# robot.net
KiCad netlist of a schematic drawn in EAGLE
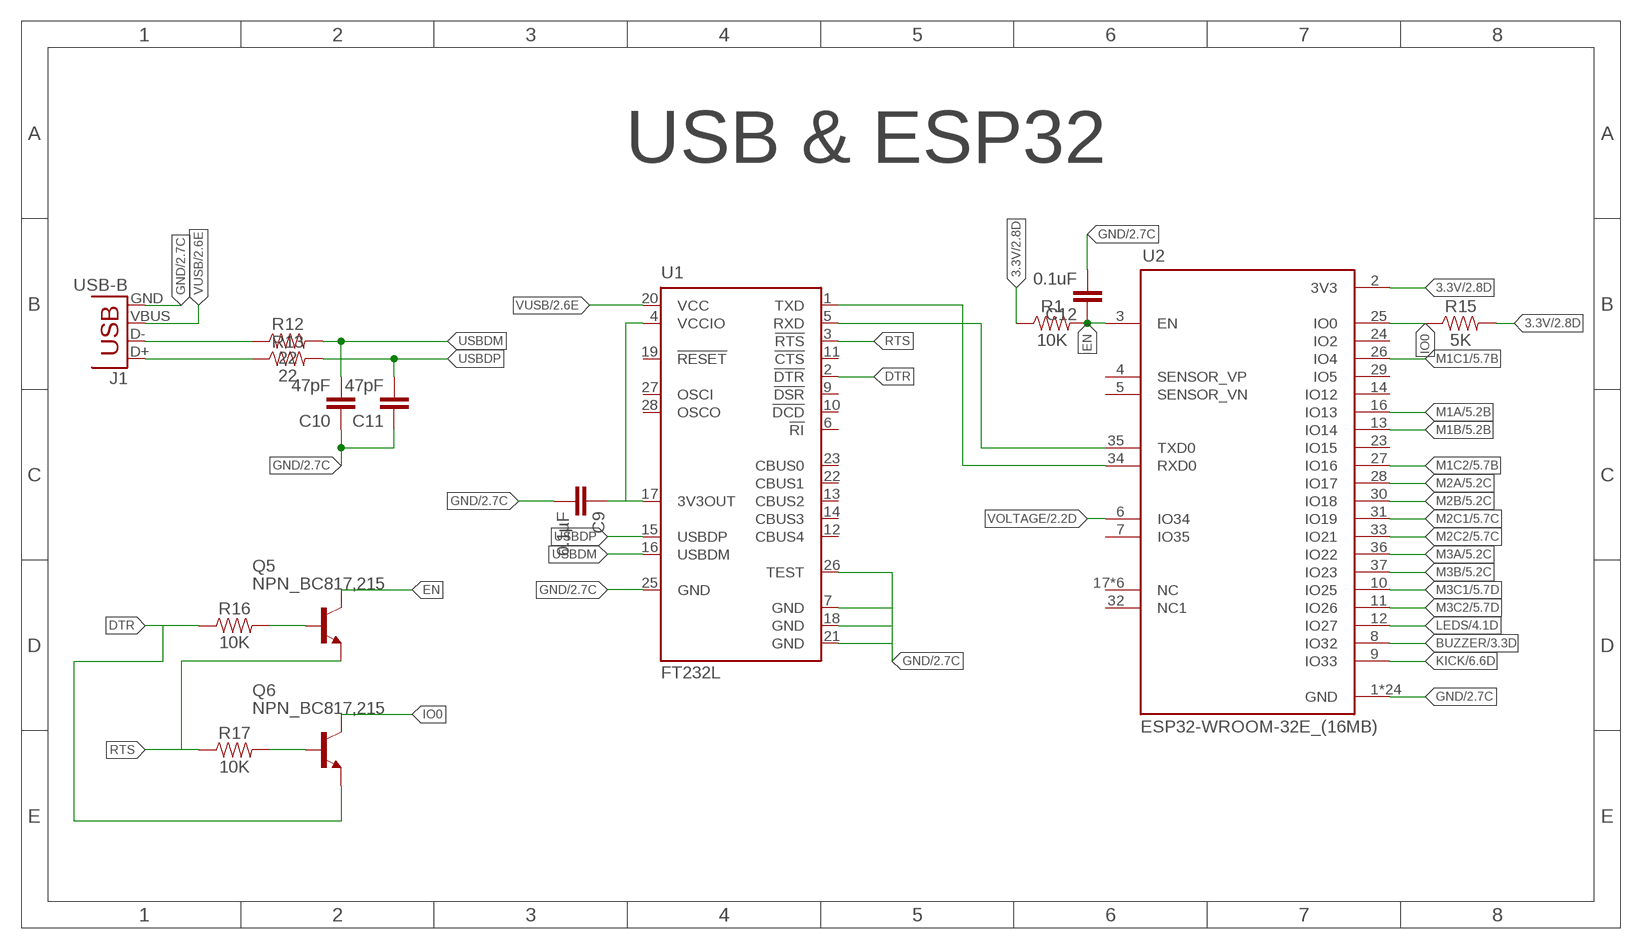
[diagram p0: schematic, sheet 1]
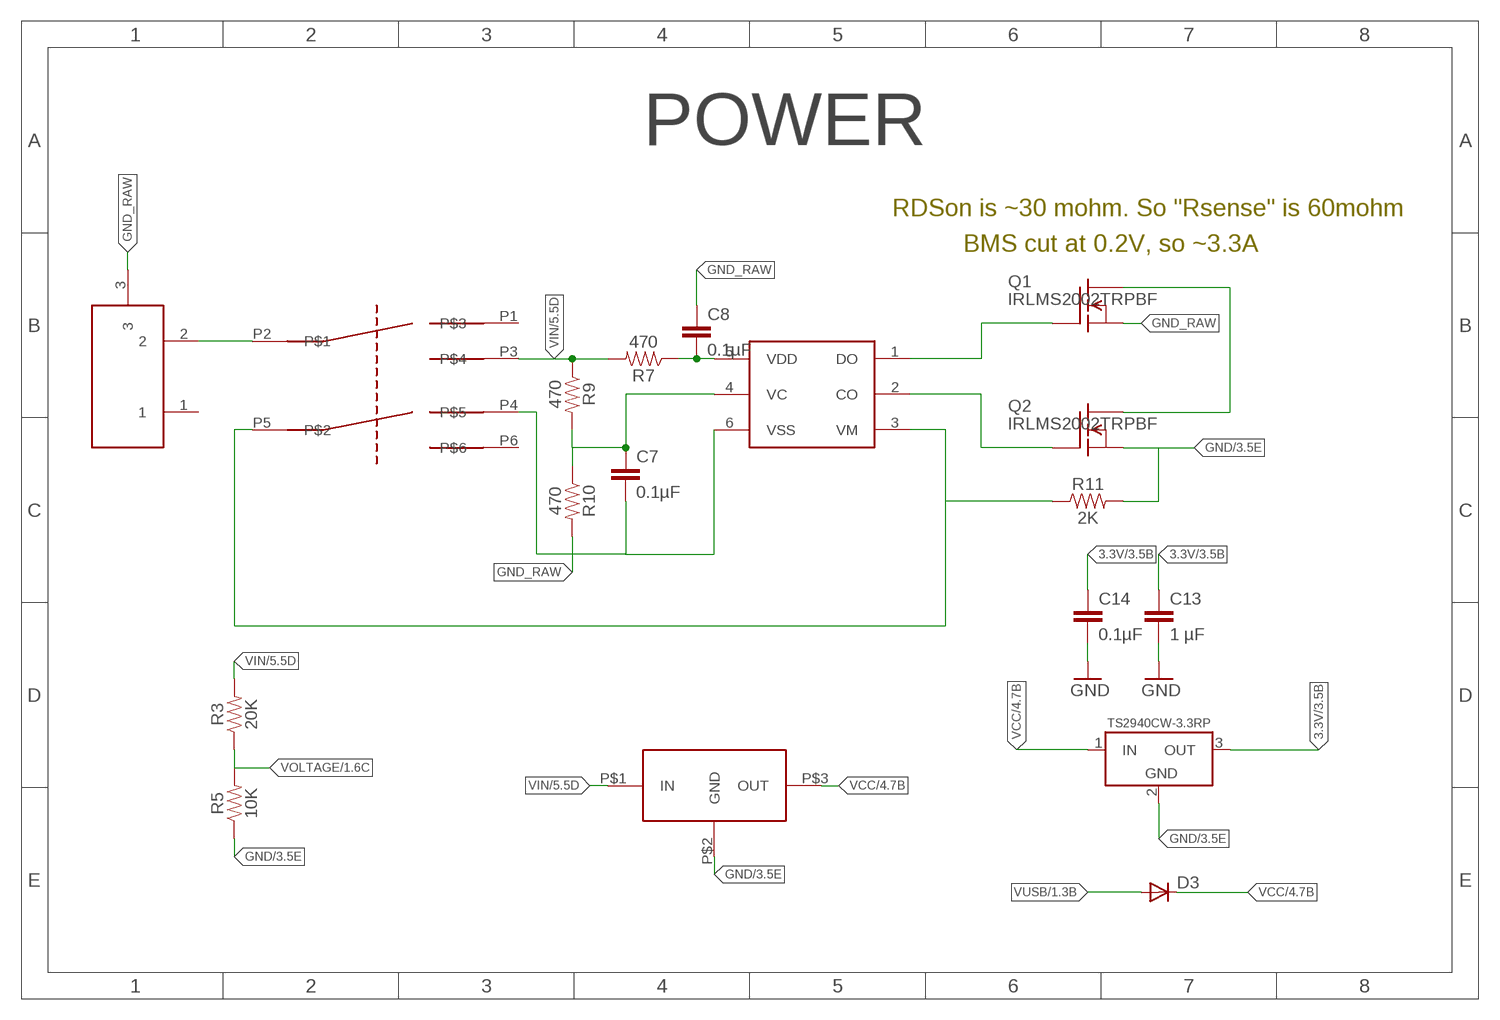
[diagram p1: schematic, sheet 2]
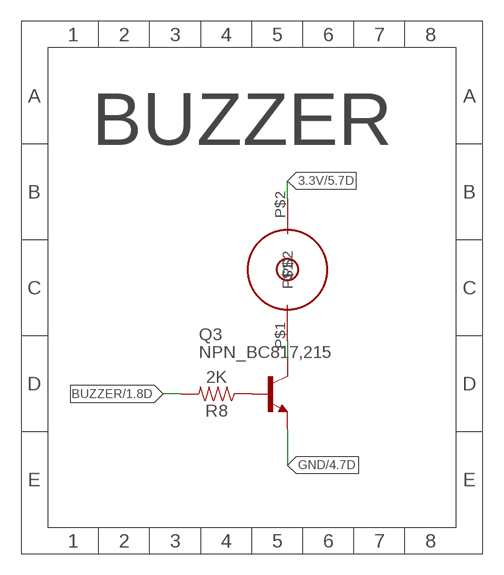
[diagram p2: schematic, sheet 3]
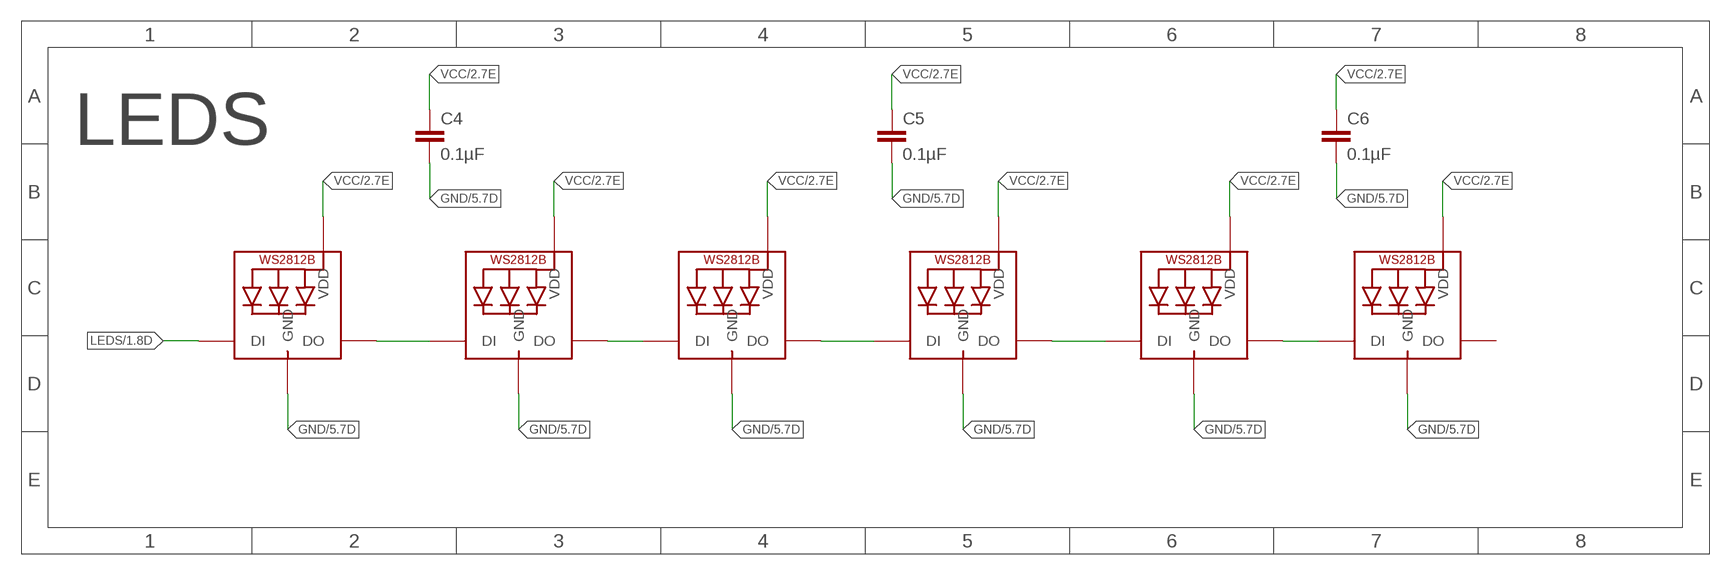
[diagram p3: schematic, sheet 4]
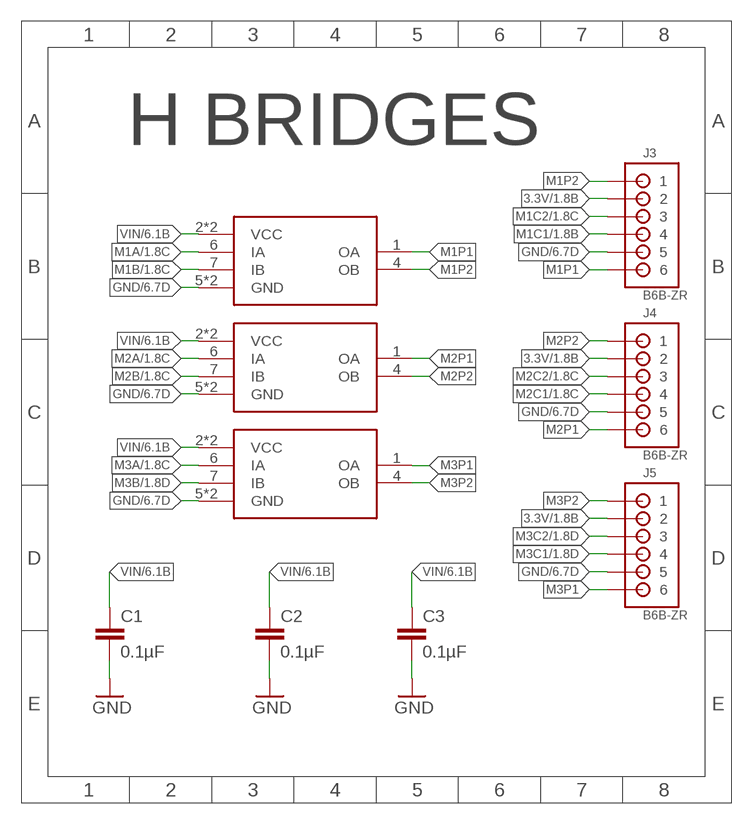
[diagram p4: schematic, sheet 5]
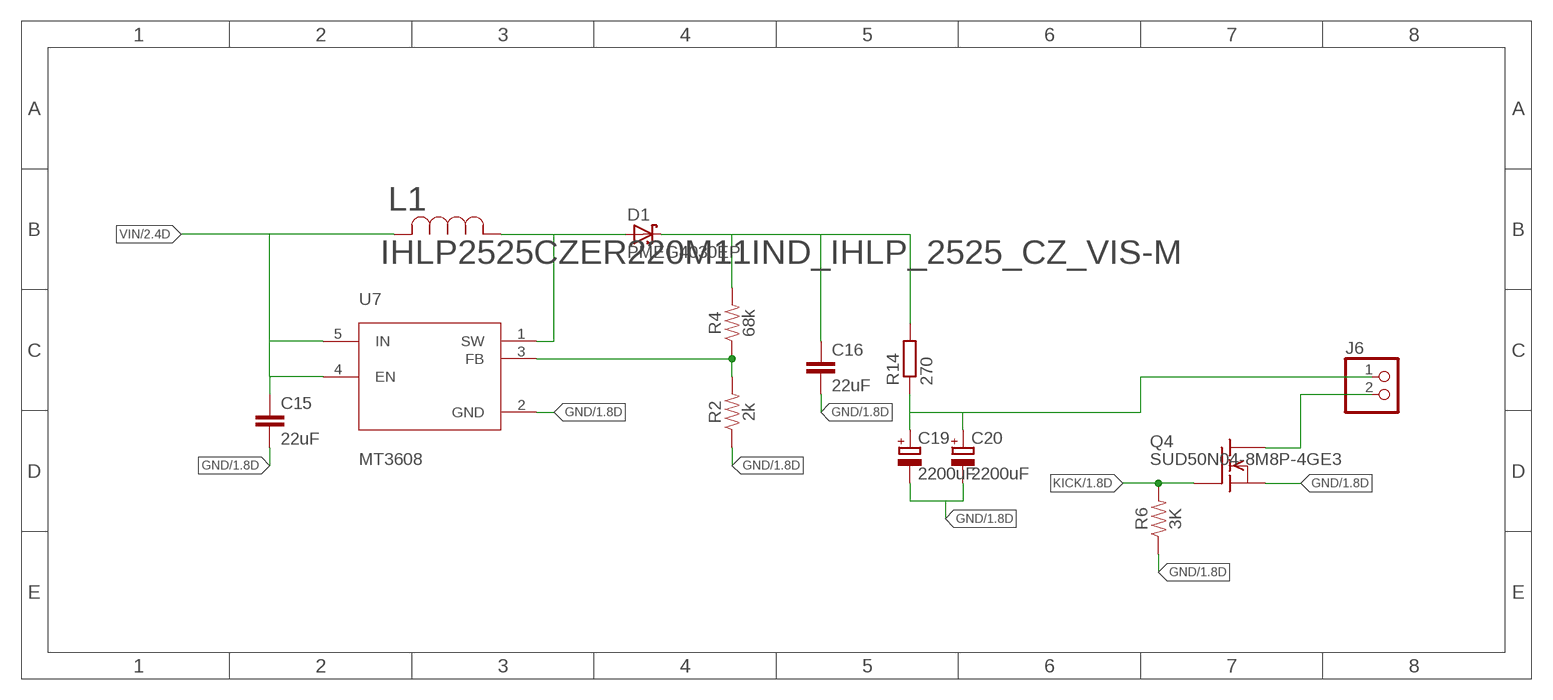
[diagram p5: schematic, sheet 6]

(export (version "E")
  (design (tool "Eeschema 10.0.6"))
  (components
    (comp (ref "C1")
      (value "0.1µF")
      (footprint "eagle-import:0805")
      (libsource (lib "eagle-import") (part "0.33UF/330NF-0805-50V-10%"))
    )
    (comp (ref "C2")
      (value "0.1µF")
      (footprint "eagle-import:0805")
      (fields (field (name "PROD_ID") "CAP-08469"))
      (libsource (lib "eagle-import") (part "0.33UF/330NF-0805-50V-10%"))
    )
    (comp (ref "C3")
      (value "0.1µF")
      (footprint "eagle-import:0805")
      (fields (field (name "PROD_ID") "CAP-08469"))
      (libsource (lib "eagle-import") (part "0.33UF/330NF-0805-50V-10%"))
    )
    (comp (ref "J3")
      (value "B6B-ZR")
      (footprint "eagle-import:B6B-ZR")
      (libsource (lib "eagle-import") (part "B6B-ZR"))
    )
    (comp (ref "J4")
      (value "B6B-ZR")
      (footprint "eagle-import:B6B-ZR")
      (libsource (lib "eagle-import") (part "B6B-ZR"))
    )
    (comp (ref "J5")
      (value "B6B-ZR")
      (footprint "eagle-import:B6B-ZR")
      (libsource (lib "eagle-import") (part "B6B-ZR"))
    )
    (comp (ref "U4")
      (value "L9110")
      (footprint "eagle-import:SO8")
      (libsource (lib "eagle-import") (part "L9110"))
    )
    (comp (ref "U5")
      (value "L9110")
      (footprint "eagle-import:SO8")
      (libsource (lib "eagle-import") (part "L9110"))
    )
    (comp (ref "U6")
      (value "L9110")
      (footprint "eagle-import:SO8")
      (libsource (lib "eagle-import") (part "L9110"))
    )
    (comp (ref "B1")
      (value "BUZZER66")
      (footprint "eagle-import:BUZZER66")
      (libsource (lib "eagle-import") (part "BUZZER66"))
    )
    (comp (ref "Q3")
      (value "NPN_BC817,215")
      (footprint "eagle-import:SOT-23")
      (libsource (lib "eagle-import") (part "NPN_BC817,215"))
    )
    (comp (ref "R8")
      (value "2K")
      (footprint "eagle-import:0805")
      (libsource (lib "eagle-import") (part "0.3OHM-0805-1/8W-1%"))
    )
    (comp (ref "C9")
      (value "0.1µF")
      (footprint "eagle-import:0805")
      (libsource (lib "eagle-import") (part "0.33UF/330NF-0805-50V-10%"))
    )
    (comp (ref "C10")
      (value "47pF")
      (footprint "eagle-import:0805")
      (libsource (lib "eagle-import") (part "CAP0805"))
    )
    (comp (ref "C11")
      (value "47pF")
      (footprint "eagle-import:0805")
      (libsource (lib "eagle-import") (part "CAP0805"))
    )
    (comp (ref "C12")
      (value "0.1uF")
      (footprint "eagle-import:0805")
      (libsource (lib "eagle-import") (part "CAP0805"))
    )
    (comp (ref "J1")
      (value "USB-B")
      (footprint "eagle-import:USB-B-PTH")
      (libsource (lib "eagle-import") (part "USBPTH"))
    )
    (comp (ref "Q5")
      (value "NPN_BC817,215")
      (footprint "eagle-import:SOT-23")
      (libsource (lib "eagle-import") (part "NPN_BC817,215"))
    )
    (comp (ref "Q6")
      (value "NPN_BC817,215")
      (footprint "eagle-import:SOT-23")
      (libsource (lib "eagle-import") (part "NPN_BC817,215"))
    )
    (comp (ref "R1")
      (value "10K")
      (footprint "eagle-import:0805")
      (fields (field (name "PROD_ID") "RES-11622"))
      (libsource (lib "eagle-import") (part "0.3OHM-0805-1/8W-1%"))
    )
    (comp (ref "R12")
      (value "22")
      (footprint "eagle-import:0805")
      (libsource (lib "eagle-import") (part "0.3OHM-0805-1/8W-1%"))
    )
    (comp (ref "R13")
      (value "22")
      (footprint "eagle-import:0805")
      (fields (field (name "PROD_ID") "RES-11622"))
      (libsource (lib "eagle-import") (part "0.3OHM-0805-1/8W-1%"))
    )
    (comp (ref "R15")
      (value "5K")
      (footprint "eagle-import:0805")
      (fields (field (name "PROD_ID") "RES-11622"))
      (libsource (lib "eagle-import") (part "0.3OHM-0805-1/8W-1%"))
    )
    (comp (ref "R16")
      (value "10K")
      (footprint "eagle-import:0805")
      (fields (field (name "PROD_ID") "RES-11622"))
      (libsource (lib "eagle-import") (part "0.3OHM-0805-1/8W-1%"))
    )
    (comp (ref "R17")
      (value "10K")
      (footprint "eagle-import:0805")
      (fields (field (name "PROD_ID") "RES-11622"))
      (libsource (lib "eagle-import") (part "0.3OHM-0805-1/8W-1%"))
    )
    (comp (ref "U1")
      (value "FT232L")
      (footprint "eagle-import:SSOP28")
      (fields (field (name "MPN") "FT232RL"))
      (libsource (lib "eagle-import") (part "FT232L"))
    )
    (comp (ref "U2")
      (value "ESP32-WROOM-32E_(16MB)")
      (footprint "eagle-import:MODULE_ESP32-WROOM-32E_(16MB)")
      (fields (field (name "MF") "Espressif Systems") (field (name "MP") "ESP32-WROOM-32E (16MB)"))
      (libsource (lib "eagle-import") (part "ESP32-WROOM-32E_(16MB)"))
    )
    (comp (ref "C4")
      (value "0.1µF")
      (footprint "eagle-import:0805")
      (libsource (lib "eagle-import") (part "0.33UF/330NF-0805-50V-10%"))
    )
    (comp (ref "C5")
      (value "0.1µF")
      (footprint "eagle-import:0805")
      (fields (field (name "PROD_ID") "CAP-08469"))
      (libsource (lib "eagle-import") (part "0.33UF/330NF-0805-50V-10%"))
    )
    (comp (ref "C6")
      (value "0.1µF")
      (footprint "eagle-import:0805")
      (fields (field (name "PROD_ID") "CAP-08469"))
      (libsource (lib "eagle-import") (part "0.33UF/330NF-0805-50V-10%"))
    )
    (comp (ref "LED1")
      (value "WS2812B5050")
      (footprint "eagle-import:WS2812B")
      (libsource (lib "eagle-import") (part "WS2812B5050"))
    )
    (comp (ref "LED2")
      (value "WS2812B5050")
      (footprint "eagle-import:WS2812B")
      (libsource (lib "eagle-import") (part "WS2812B5050"))
    )
    (comp (ref "LED3")
      (value "WS2812B5050")
      (footprint "eagle-import:WS2812B")
      (libsource (lib "eagle-import") (part "WS2812B5050"))
    )
    (comp (ref "LED4")
      (value "WS2812B5050")
      (footprint "eagle-import:WS2812B")
      (libsource (lib "eagle-import") (part "WS2812B5050"))
    )
    (comp (ref "LED5")
      (value "WS2812B5050")
      (footprint "eagle-import:WS2812B")
      (libsource (lib "eagle-import") (part "WS2812B5050"))
    )
    (comp (ref "LED6")
      (value "WS2812B5050")
      (footprint "eagle-import:WS2812B")
      (libsource (lib "eagle-import") (part "WS2812B5050"))
    )
    (comp (ref "C15")
      (value "22uF")
      (footprint "eagle-import:C0805")
      (libsource (lib "eagle-import") (part "C-EUC0805"))
    )
    (comp (ref "C16")
      (value "22uF")
      (footprint "eagle-import:C0805")
      (libsource (lib "eagle-import") (part "C-EUC0805"))
    )
    (comp (ref "C19")
      (value "2200uF")
      (footprint "eagle-import:E5-13")
      (libsource (lib "eagle-import") (part "CPOL-EUE5-13"))
    )
    (comp (ref "C20")
      (value "2200uF")
      (footprint "eagle-import:E5-13")
      (libsource (lib "eagle-import") (part "CPOL-EUE5-13"))
    )
    (comp (ref "D1")
      (value "PMEG4030EP")
      (footprint "eagle-import:SOD128")
      (libsource (lib "eagle-import") (part "PMEG4030EP"))
    )
    (comp (ref "J6")
      (value "KICKER")
      (footprint "eagle-import:KICKER")
      (libsource (lib "eagle-import") (part "KICKER"))
    )
    (comp (ref "L1")
      (value "IHLP2525CZER220M11IND_IHLP_2525_CZ_VIS-M")
      (footprint "eagle-import:IND_IHLP_2525_CZ_VIS-M")
      (fields (field (name "MANUFACTURER_PART_NUMBER") "IHLP2525CZER220M11"))
      (libsource (lib "eagle-import") (part "IHLP2525CZER220M11IND_IHLP_2525_CZ_VIS-M"))
    )
    (comp (ref "Q4")
      (value "SUD50N04-8M8P-4GE3")
      (footprint "eagle-import:TO252")
      (libsource (lib "eagle-import") (part "SUD50N04-8M8P-4GE3"))
    )
    (comp (ref "R2")
      (value "2k")
      (footprint "eagle-import:0805")
      (libsource (lib "eagle-import") (part "0.3OHM-0805-1/8W-1%"))
    )
    (comp (ref "R4")
      (value "68k")
      (footprint "eagle-import:0805")
      (libsource (lib "eagle-import") (part "0.3OHM-0805-1/8W-1%"))
    )
    (comp (ref "R6")
      (value "3K")
      (footprint "eagle-import:0805")
      (fields (field (name "PROD_ID") "RES-11622"))
      (libsource (lib "eagle-import") (part "0.3OHM-0805-1/8W-1%"))
    )
    (comp (ref "R14")
      (value "270")
      (footprint "eagle-import:R2010")
      (libsource (lib "eagle-import") (part "R-EU_R2010"))
    )
    (comp (ref "U7")
      (value "MT3608")
      (footprint "eagle-import:SOT95P280X145-6N")
      (fields (field (name "MF") "Aerosemi Technology Co., Ltd"))
      (libsource (lib "eagle-import") (part "MT3608"))
    )
    (comp (ref "C7")
      (value "0.1µF")
      (footprint "eagle-import:0805")
      (libsource (lib "eagle-import") (part "0.33UF/330NF-0805-50V-10%"))
    )
    (comp (ref "C8")
      (value "0.1µF")
      (footprint "eagle-import:0805")
      (fields (field (name "PROD_ID") "CAP-08469"))
      (libsource (lib "eagle-import") (part "0.33UF/330NF-0805-50V-10%"))
    )
    (comp (ref "C13")
      (value "1 µF")
      (footprint "eagle-import:0805")
      (fields (field (name "PROD_ID") "CAP-08469"))
      (libsource (lib "eagle-import") (part "0.33UF/330NF-0805-50V-10%"))
    )
    (comp (ref "C14")
      (value "0.1µF")
      (footprint "eagle-import:0805")
      (fields (field (name "PROD_ID") "CAP-08469"))
      (libsource (lib "eagle-import") (part "0.33UF/330NF-0805-50V-10%"))
    )
    (comp (ref "D3")
      (value "DIODESOD")
      (footprint "eagle-import:SOD-323")
      (libsource (lib "eagle-import") (part "DIODESOD"))
    )
    (comp (ref "J2")
      (value "DC21MMX")
      (footprint "eagle-import:DC-21MM")
      (libsource (lib "eagle-import") (part "DC21MMX"))
    )
    (comp (ref "Q1")
      (value "IRLMS2002TRPBF")
      (footprint "eagle-import:SOT23-6")
      (libsource (lib "eagle-import") (part "IRLMS2002TRPBF"))
    )
    (comp (ref "Q2")
      (value "IRLMS2002TRPBF")
      (footprint "eagle-import:SOT23-6")
      (libsource (lib "eagle-import") (part "IRLMS2002TRPBF"))
    )
    (comp (ref "R3")
      (value "20K")
      (footprint "eagle-import:0805")
      (libsource (lib "eagle-import") (part "0.3OHM-0805-1/8W-1%"))
    )
    (comp (ref "R5")
      (value "10K")
      (footprint "eagle-import:0805")
      (libsource (lib "eagle-import") (part "0.3OHM-0805-1/8W-1%"))
    )
    (comp (ref "R7")
      (value "470")
      (footprint "eagle-import:0805")
      (libsource (lib "eagle-import") (part "0.3OHM-0805-1/8W-1%"))
    )
    (comp (ref "R9")
      (value "470")
      (footprint "eagle-import:0805")
      (libsource (lib "eagle-import") (part "0.3OHM-0805-1/8W-1%"))
    )
    (comp (ref "R10")
      (value "470")
      (footprint "eagle-import:0805")
      (libsource (lib "eagle-import") (part "0.3OHM-0805-1/8W-1%"))
    )
    (comp (ref "R11")
      (value "2K")
      (footprint "eagle-import:0805")
      (libsource (lib "eagle-import") (part "0.3OHM-0805-1/8W-1%"))
    )
    (comp (ref "REG1")
      (value "REG_5V")
      (footprint "eagle-import:TRACOPOWER")
      (libsource (lib "eagle-import") (part "REG_5V"))
    )
    (comp (ref "S1")
      (value "DPDT")
      (footprint "eagle-import:L202021MA04Q")
      (libsource (lib "eagle-import") (part "DPDT"))
    )
    (comp (ref "U$25")
      (value "TS2940CW-3.3RP")
      (footprint "eagle-import:SOT223")
      (libsource (lib "eagle-import") (part "TS2940CW-3.3RP"))
    )
    (comp (ref "U3")
      (value "S8252")
      (footprint "eagle-import:SOT23-6")
      (libsource (lib "eagle-import") (part "S8252"))
    )
  )
  (nets
    (net (code "1") (name "1") (class "Default")
      (node (ref "J2") (pin "1") (pinfunction "1_1") (pintype "power_in"))
    )
    (net (code "2") (name "3.3V") (class "Default")
      (node (ref "B1") (pin "P$2") (pinfunction "P$2_P$2") (pintype "bidirectional"))
      (node (ref "C13") (pin "1") (pinfunction "1_1") (pintype "passive"))
      (node (ref "C14") (pin "1") (pinfunction "1_1") (pintype "passive"))
      (node (ref "J3") (pin "2") (pinfunction "2_2") (pintype "bidirectional"))
      (node (ref "J4") (pin "2") (pinfunction "2_2") (pintype "bidirectional"))
      (node (ref "J5") (pin "2") (pinfunction "2_2") (pintype "bidirectional"))
      (node (ref "R1") (pin "1") (pinfunction "1_1") (pintype "passive"))
      (node (ref "R15") (pin "2") (pinfunction "2_2") (pintype "passive"))
      (node (ref "U$25") (pin "3") (pinfunction "OUT_3") (pintype "output"))
      (node (ref "U2") (pin "2") (pinfunction "3V3_2") (pintype "power_in"))
    )
    (net (code "3") (name "BUZZER") (class "Default")
      (node (ref "R8") (pin "2") (pinfunction "2_2") (pintype "passive"))
      (node (ref "U2") (pin "8") (pinfunction "IO32_8") (pintype "bidirectional"))
    )
    (net (code "4") (name "DTR") (class "Default")
      (node (ref "Q6") (pin "2") (pinfunction "E_2") (pintype "passive"))
      (node (ref "R16") (pin "1") (pinfunction "1_1") (pintype "passive"))
      (node (ref "U1") (pin "2") (pinfunction "~{DTR}_2") (pintype "output"))
    )
    (net (code "5") (name "EN") (class "Default")
      (node (ref "C12") (pin "1") (pinfunction "1_1") (pintype "passive"))
      (node (ref "Q5") (pin "3") (pinfunction "C_3") (pintype "passive"))
      (node (ref "R1") (pin "2") (pinfunction "2_2") (pintype "passive"))
      (node (ref "U2") (pin "3") (pinfunction "EN_3") (pintype "input"))
    )
    (net (code "6") (name "GND") (class "Default")
      (node (ref "C1") (pin "2") (pinfunction "2_2") (pintype "passive"))
      (node (ref "C10") (pin "1") (pinfunction "1_1") (pintype "passive"))
      (node (ref "C11") (pin "1") (pinfunction "1_1") (pintype "passive"))
      (node (ref "C12") (pin "2") (pinfunction "2_2") (pintype "passive"))
      (node (ref "C13") (pin "2") (pinfunction "2_2") (pintype "passive"))
      (node (ref "C14") (pin "2") (pinfunction "2_2") (pintype "passive"))
      (node (ref "C15") (pin "2") (pinfunction "2_2") (pintype "passive"))
      (node (ref "C16") (pin "2") (pinfunction "2_2") (pintype "passive"))
      (node (ref "C19") (pin "-") (pinfunction "-_-") (pintype "passive"))
      (node (ref "C2") (pin "2") (pinfunction "2_2") (pintype "passive"))
      (node (ref "C20") (pin "-") (pinfunction "-_-") (pintype "passive"))
      (node (ref "C3") (pin "2") (pinfunction "2_2") (pintype "passive"))
      (node (ref "C4") (pin "2") (pinfunction "2_2") (pintype "passive"))
      (node (ref "C5") (pin "2") (pinfunction "2_2") (pintype "passive"))
      (node (ref "C6") (pin "2") (pinfunction "2_2") (pintype "passive"))
      (node (ref "C9") (pin "2") (pinfunction "2_2") (pintype "passive"))
      (node (ref "J1") (pin "GND") (pinfunction "GND_GND") (pintype "bidirectional"))
      (node (ref "J3") (pin "5") (pinfunction "5_5") (pintype "bidirectional"))
      (node (ref "J4") (pin "5") (pinfunction "5_5") (pintype "bidirectional"))
      (node (ref "J5") (pin "5") (pinfunction "5_5") (pintype "bidirectional"))
      (node (ref "LED1") (pin "3-GND") (pinfunction "GND_3-GND") (pintype "power_in"))
      (node (ref "LED2") (pin "3-GND") (pinfunction "GND_3-GND") (pintype "power_in"))
      (node (ref "LED3") (pin "3-GND") (pinfunction "GND_3-GND") (pintype "power_in"))
      (node (ref "LED4") (pin "3-GND") (pinfunction "GND_3-GND") (pintype "power_in"))
      (node (ref "LED5") (pin "3-GND") (pinfunction "GND_3-GND") (pintype "power_in"))
      (node (ref "LED6") (pin "3-GND") (pinfunction "GND_3-GND") (pintype "power_in"))
      (node (ref "Q2") (pin "4") (pinfunction "S_4") (pintype "passive"))
      (node (ref "Q3") (pin "2") (pinfunction "E_2") (pintype "passive"))
      (node (ref "Q4") (pin "2") (pinfunction "S_2") (pintype "passive"))
      (node (ref "R11") (pin "2") (pinfunction "2_2") (pintype "passive"))
      (node (ref "R2") (pin "1") (pinfunction "1_1") (pintype "passive"))
      (node (ref "R5") (pin "1") (pinfunction "1_1") (pintype "passive"))
      (node (ref "R6") (pin "1") (pinfunction "1_1") (pintype "passive"))
      (node (ref "REG1") (pin "P$2") (pinfunction "GND_P$2") (pintype "bidirectional"))
      (node (ref "U$25") (pin "2") (pinfunction "GND_2") (pintype "power_in"))
      (node (ref "U1") (pin "18") (pinfunction "GND_18") (pintype "power_in"))
      (node (ref "U1") (pin "21") (pinfunction "GND_21") (pintype "power_in"))
      (node (ref "U1") (pin "25") (pinfunction "GND_25") (pintype "power_in"))
      (node (ref "U1") (pin "26") (pinfunction "TEST_26") (pintype "input"))
      (node (ref "U1") (pin "7") (pinfunction "GND_7") (pintype "power_in"))
      (node (ref "U2") (pin "1") (pinfunction "GND_1") (pintype "power_in"))
      (node (ref "U2") (pin "15") (pinfunction "GND_15") (pintype "power_in"))
      (node (ref "U2") (pin "38") (pinfunction "GND_38") (pintype "power_in"))
      (node (ref "U2") (pin "39_1") (pinfunction "GND_39_1") (pintype "power_in"))
      (node (ref "U2") (pin "39_10") (pinfunction "GND_39_10") (pintype "power_in"))
      (node (ref "U2") (pin "39_11") (pinfunction "GND_39_11") (pintype "power_in"))
      (node (ref "U2") (pin "39_12") (pinfunction "GND_39_12") (pintype "power_in"))
      (node (ref "U2") (pin "39_13") (pinfunction "GND_39_13") (pintype "power_in"))
      (node (ref "U2") (pin "39_14") (pinfunction "GND_39_14") (pintype "power_in"))
      (node (ref "U2") (pin "39_15") (pinfunction "GND_39_15") (pintype "power_in"))
      (node (ref "U2") (pin "39_16") (pinfunction "GND_39_16") (pintype "power_in"))
      (node (ref "U2") (pin "39_17") (pinfunction "GND_39_17") (pintype "power_in"))
      (node (ref "U2") (pin "39_18") (pinfunction "GND_39_18") (pintype "power_in"))
      (node (ref "U2") (pin "39_19") (pinfunction "GND_39_19") (pintype "power_in"))
      (node (ref "U2") (pin "39_2") (pinfunction "GND_39_2") (pintype "power_in"))
      (node (ref "U2") (pin "39_20") (pinfunction "GND_39_20") (pintype "power_in"))
      (node (ref "U2") (pin "39_21") (pinfunction "GND_39_21") (pintype "power_in"))
      (node (ref "U2") (pin "39_3") (pinfunction "GND_39_3") (pintype "power_in"))
      (node (ref "U2") (pin "39_4") (pinfunction "GND_39_4") (pintype "power_in"))
      (node (ref "U2") (pin "39_5") (pinfunction "GND_39_5") (pintype "power_in"))
      (node (ref "U2") (pin "39_6") (pinfunction "GND_39_6") (pintype "power_in"))
      (node (ref "U2") (pin "39_7") (pinfunction "GND_39_7") (pintype "power_in"))
      (node (ref "U2") (pin "39_8") (pinfunction "GND_39_8") (pintype "power_in"))
      (node (ref "U2") (pin "39_9") (pinfunction "GND_39_9") (pintype "power_in"))
      (node (ref "U4") (pin "5") (pinfunction "GND_5") (pintype "bidirectional"))
      (node (ref "U4") (pin "8") (pinfunction "GND_8") (pintype "bidirectional"))
      (node (ref "U5") (pin "5") (pinfunction "GND_5") (pintype "bidirectional"))
      (node (ref "U5") (pin "8") (pinfunction "GND_8") (pintype "bidirectional"))
      (node (ref "U6") (pin "5") (pinfunction "GND_5") (pintype "bidirectional"))
      (node (ref "U6") (pin "8") (pinfunction "GND_8") (pintype "bidirectional"))
      (node (ref "U7") (pin "2") (pinfunction "GND_2") (pintype "power_in"))
    )
    (net (code "7") (name "GND_RAW") (class "Default")
      (node (ref "C7") (pin "2") (pinfunction "2_2") (pintype "passive"))
      (node (ref "C8") (pin "1") (pinfunction "1_1") (pintype "passive"))
      (node (ref "J2") (pin "3") (pinfunction "3_3") (pintype "power_in"))
      (node (ref "Q1") (pin "4") (pinfunction "S_4") (pintype "passive"))
      (node (ref "R10") (pin "2") (pinfunction "2_2") (pintype "passive"))
      (node (ref "S1") (pin "P4") (pinfunction "P$5_P4") (pintype "bidirectional"))
      (node (ref "U3") (pin "6") (pinfunction "VSS_6") (pintype "passive"))
    )
    (net (code "8") (name "IO0") (class "Default")
      (node (ref "Q6") (pin "3") (pinfunction "C_3") (pintype "passive"))
      (node (ref "R15") (pin "1") (pinfunction "1_1") (pintype "passive"))
      (node (ref "U2") (pin "25") (pinfunction "IO0_25") (pintype "bidirectional"))
    )
    (net (code "9") (name "KICK") (class "Default")
      (node (ref "Q4") (pin "1") (pinfunction "G_1") (pintype "passive"))
      (node (ref "R6") (pin "2") (pinfunction "2_2") (pintype "passive"))
      (node (ref "U2") (pin "9") (pinfunction "IO33_9") (pintype "bidirectional"))
    )
    (net (code "10") (name "LEDS") (class "Default")
      (node (ref "LED1") (pin "4-DIN") (pinfunction "DI_4-DIN") (pintype "input"))
      (node (ref "U2") (pin "12") (pinfunction "IO27_12") (pintype "bidirectional"))
    )
    (net (code "11") (name "M1A") (class "Default")
      (node (ref "U2") (pin "16") (pinfunction "IO13_16") (pintype "bidirectional"))
      (node (ref "U4") (pin "6") (pinfunction "IA_6") (pintype "bidirectional"))
    )
    (net (code "12") (name "M1B") (class "Default")
      (node (ref "U2") (pin "13") (pinfunction "IO14_13") (pintype "bidirectional"))
      (node (ref "U4") (pin "7") (pinfunction "IB_7") (pintype "bidirectional"))
    )
    (net (code "13") (name "M1C1") (class "Default")
      (node (ref "J3") (pin "4") (pinfunction "4_4") (pintype "bidirectional"))
      (node (ref "U2") (pin "26") (pinfunction "IO4_26") (pintype "bidirectional"))
    )
    (net (code "14") (name "M1C2") (class "Default")
      (node (ref "J3") (pin "3") (pinfunction "3_3") (pintype "bidirectional"))
      (node (ref "U2") (pin "27") (pinfunction "IO16_27") (pintype "bidirectional"))
    )
    (net (code "15") (name "M1P1") (class "Default")
      (node (ref "J3") (pin "6") (pinfunction "6_6") (pintype "bidirectional"))
      (node (ref "U4") (pin "1") (pinfunction "OA_1") (pintype "bidirectional"))
    )
    (net (code "16") (name "M1P2") (class "Default")
      (node (ref "J3") (pin "1") (pinfunction "1_1") (pintype "bidirectional"))
      (node (ref "U4") (pin "4") (pinfunction "OB_4") (pintype "bidirectional"))
    )
    (net (code "17") (name "M2A") (class "Default")
      (node (ref "U2") (pin "28") (pinfunction "IO17_28") (pintype "bidirectional"))
      (node (ref "U5") (pin "6") (pinfunction "IA_6") (pintype "bidirectional"))
    )
    (net (code "18") (name "M2B") (class "Default")
      (node (ref "U2") (pin "30") (pinfunction "IO18_30") (pintype "bidirectional"))
      (node (ref "U5") (pin "7") (pinfunction "IB_7") (pintype "bidirectional"))
    )
    (net (code "19") (name "M2C1") (class "Default")
      (node (ref "J4") (pin "4") (pinfunction "4_4") (pintype "bidirectional"))
      (node (ref "U2") (pin "31") (pinfunction "IO19_31") (pintype "bidirectional"))
    )
    (net (code "20") (name "M2C2") (class "Default")
      (node (ref "J4") (pin "3") (pinfunction "3_3") (pintype "bidirectional"))
      (node (ref "U2") (pin "33") (pinfunction "IO21_33") (pintype "bidirectional"))
    )
    (net (code "21") (name "M2P1") (class "Default")
      (node (ref "J4") (pin "6") (pinfunction "6_6") (pintype "bidirectional"))
      (node (ref "U5") (pin "1") (pinfunction "OA_1") (pintype "bidirectional"))
    )
    (net (code "22") (name "M2P2") (class "Default")
      (node (ref "J4") (pin "1") (pinfunction "1_1") (pintype "bidirectional"))
      (node (ref "U5") (pin "4") (pinfunction "OB_4") (pintype "bidirectional"))
    )
    (net (code "23") (name "M3A") (class "Default")
      (node (ref "U2") (pin "36") (pinfunction "IO22_36") (pintype "bidirectional"))
      (node (ref "U6") (pin "6") (pinfunction "IA_6") (pintype "bidirectional"))
    )
    (net (code "24") (name "M3B") (class "Default")
      (node (ref "U2") (pin "37") (pinfunction "IO23_37") (pintype "bidirectional"))
      (node (ref "U6") (pin "7") (pinfunction "IB_7") (pintype "bidirectional"))
    )
    (net (code "25") (name "M3C1") (class "Default")
      (node (ref "J5") (pin "4") (pinfunction "4_4") (pintype "bidirectional"))
      (node (ref "U2") (pin "10") (pinfunction "IO25_10") (pintype "bidirectional"))
    )
    (net (code "26") (name "M3C2") (class "Default")
      (node (ref "J5") (pin "3") (pinfunction "3_3") (pintype "bidirectional"))
      (node (ref "U2") (pin "11") (pinfunction "IO26_11") (pintype "bidirectional"))
    )
    (net (code "27") (name "M3P1") (class "Default")
      (node (ref "J5") (pin "6") (pinfunction "6_6") (pintype "bidirectional"))
      (node (ref "U6") (pin "1") (pinfunction "OA_1") (pintype "bidirectional"))
    )
    (net (code "28") (name "M3P2") (class "Default")
      (node (ref "J5") (pin "1") (pinfunction "1_1") (pintype "bidirectional"))
      (node (ref "U6") (pin "4") (pinfunction "OB_4") (pintype "bidirectional"))
    )
    (net (code "29") (name "Net-(C19-Pad+)") (class "Default")
      (node (ref "C19") (pin "+") (pinfunction "+_+") (pintype "passive"))
      (node (ref "C20") (pin "+") (pinfunction "+_+") (pintype "passive"))
      (node (ref "J6") (pin "1") (pinfunction "1_1") (pintype "passive"))
      (node (ref "R14") (pin "1") (pinfunction "1_1") (pintype "passive"))
    )
    (net (code "30") (name "Net-(D1-A)") (class "Default")
      (node (ref "D1") (pin "2") (pinfunction "A_2") (pintype "passive"))
      (node (ref "L1") (pin "1") (pinfunction "1_1") (pintype "passive"))
      (node (ref "U7") (pin "1") (pinfunction "SW_1") (pintype "output"))
    )
    (net (code "31") (name "Net-(D1-K)") (class "Default")
      (node (ref "C16") (pin "1") (pinfunction "1_1") (pintype "passive"))
      (node (ref "D1") (pin "1") (pinfunction "K_1") (pintype "passive"))
      (node (ref "R14") (pin "2") (pinfunction "2_2") (pintype "passive"))
      (node (ref "R4") (pin "2") (pinfunction "2_2") (pintype "passive"))
    )
    (net (code "32") (name "Net-(J1-PadD+)") (class "Default")
      (node (ref "J1") (pin "D+") (pinfunction "D+_D+") (pintype "bidirectional"))
      (node (ref "R13") (pin "1") (pinfunction "1_1") (pintype "passive"))
    )
    (net (code "33") (name "Net-(J1-PadD-)") (class "Default")
      (node (ref "J1") (pin "D-") (pinfunction "D-_D-") (pintype "bidirectional"))
      (node (ref "R12") (pin "1") (pinfunction "1_1") (pintype "passive"))
    )
    (net (code "34") (name "Net-(LED1-DO)") (class "Default")
      (node (ref "LED1") (pin "2-DOUT") (pinfunction "DO_2-DOUT") (pintype "output"))
      (node (ref "LED2") (pin "4-DIN") (pinfunction "DI_4-DIN") (pintype "input"))
    )
    (net (code "35") (name "Net-(LED2-DO)") (class "Default")
      (node (ref "LED2") (pin "2-DOUT") (pinfunction "DO_2-DOUT") (pintype "output"))
      (node (ref "LED3") (pin "4-DIN") (pinfunction "DI_4-DIN") (pintype "input"))
    )
    (net (code "36") (name "Net-(LED3-DO)") (class "Default")
      (node (ref "LED3") (pin "2-DOUT") (pinfunction "DO_2-DOUT") (pintype "output"))
      (node (ref "LED4") (pin "4-DIN") (pinfunction "DI_4-DIN") (pintype "input"))
    )
    (net (code "37") (name "Net-(LED4-DO)") (class "Default")
      (node (ref "LED4") (pin "2-DOUT") (pinfunction "DO_2-DOUT") (pintype "output"))
      (node (ref "LED5") (pin "4-DIN") (pinfunction "DI_4-DIN") (pintype "input"))
    )
    (net (code "38") (name "Net-(LED5-DO)") (class "Default")
      (node (ref "LED5") (pin "2-DOUT") (pinfunction "DO_2-DOUT") (pintype "output"))
      (node (ref "LED6") (pin "4-DIN") (pinfunction "DI_4-DIN") (pintype "input"))
    )
    (net (code "39") (name "Net-(Q1-D-Pad1)") (class "Default")
      (node (ref "Q1") (pin "1") (pinfunction "D_1") (pintype "passive"))
      (node (ref "Q1") (pin "2") (pinfunction "D_2") (pintype "passive"))
      (node (ref "Q1") (pin "5") (pinfunction "D_5") (pintype "passive"))
      (node (ref "Q1") (pin "6") (pinfunction "D_6") (pintype "passive"))
      (node (ref "Q2") (pin "1") (pinfunction "D_1") (pintype "passive"))
      (node (ref "Q2") (pin "2") (pinfunction "D_2") (pintype "passive"))
      (node (ref "Q2") (pin "5") (pinfunction "D_5") (pintype "passive"))
      (node (ref "Q2") (pin "6") (pinfunction "D_6") (pintype "passive"))
    )
    (net (code "40") (name "Net-(Q1-G)") (class "Default")
      (node (ref "Q1") (pin "3") (pinfunction "G_3") (pintype "passive"))
      (node (ref "U3") (pin "1") (pinfunction "DO_1") (pintype "passive"))
    )
    (net (code "41") (name "Net-(Q2-G)") (class "Default")
      (node (ref "Q2") (pin "3") (pinfunction "G_3") (pintype "passive"))
      (node (ref "U3") (pin "2") (pinfunction "CO_2") (pintype "passive"))
    )
    (net (code "42") (name "Net-(Q3-B)") (class "Default")
      (node (ref "Q3") (pin "1") (pinfunction "B_1") (pintype "passive"))
      (node (ref "R8") (pin "1") (pinfunction "1_1") (pintype "passive"))
    )
    (net (code "43") (name "Net-(Q3-C)") (class "Default")
      (node (ref "B1") (pin "P$1") (pinfunction "P$1_P$1") (pintype "bidirectional"))
      (node (ref "Q3") (pin "3") (pinfunction "C_3") (pintype "passive"))
    )
    (net (code "44") (name "Net-(Q4-D)") (class "Default")
      (node (ref "J6") (pin "2") (pinfunction "2_2") (pintype "passive"))
      (node (ref "Q4") (pin "3") (pinfunction "D_3") (pintype "passive"))
    )
    (net (code "45") (name "Net-(Q5-B)") (class "Default")
      (node (ref "Q5") (pin "1") (pinfunction "B_1") (pintype "passive"))
      (node (ref "R16") (pin "2") (pinfunction "2_2") (pintype "passive"))
    )
    (net (code "46") (name "Net-(Q6-B)") (class "Default")
      (node (ref "Q6") (pin "1") (pinfunction "B_1") (pintype "passive"))
      (node (ref "R17") (pin "2") (pinfunction "2_2") (pintype "passive"))
    )
    (net (code "47") (name "Net-(S1-P$1)") (class "Default")
      (node (ref "J2") (pin "2") (pinfunction "2_2") (pintype "power_in"))
      (node (ref "S1") (pin "P2") (pinfunction "P$1_P2") (pintype "bidirectional"))
    )
    (net (code "48") (name "Net-(S1-P$2)") (class "Default")
      (node (ref "R11") (pin "1") (pinfunction "1_1") (pintype "passive"))
      (node (ref "S1") (pin "P5") (pinfunction "P$2_P5") (pintype "bidirectional"))
      (node (ref "U3") (pin "3") (pinfunction "VM_3") (pintype "passive"))
    )
    (net (code "49") (name "Net-(U1-3V3OUT)") (class "Default")
      (node (ref "C9") (pin "1") (pinfunction "1_1") (pintype "passive"))
      (node (ref "U1") (pin "17") (pinfunction "3V3OUT_17") (pintype "output"))
      (node (ref "U1") (pin "4") (pinfunction "VCCIO_4") (pintype "power_in"))
    )
    (net (code "50") (name "Net-(U1-RXD)") (class "Default")
      (node (ref "U1") (pin "5") (pinfunction "RXD_5") (pintype "input"))
      (node (ref "U2") (pin "35") (pinfunction "TXD0_35") (pintype "bidirectional"))
    )
    (net (code "51") (name "Net-(U1-TXD)") (class "Default")
      (node (ref "U1") (pin "1") (pinfunction "TXD_1") (pintype "output"))
      (node (ref "U2") (pin "34") (pinfunction "RXD0_34") (pintype "bidirectional"))
    )
    (net (code "52") (name "Net-(U3-VC)") (class "Default")
      (node (ref "C7") (pin "1") (pinfunction "1_1") (pintype "passive"))
      (node (ref "R10") (pin "1") (pinfunction "1_1") (pintype "passive"))
      (node (ref "R9") (pin "2") (pinfunction "2_2") (pintype "passive"))
      (node (ref "U3") (pin "4") (pinfunction "VC_4") (pintype "passive"))
    )
    (net (code "53") (name "Net-(U3-VDD)") (class "Default")
      (node (ref "C8") (pin "2") (pinfunction "2_2") (pintype "passive"))
      (node (ref "R7") (pin "1") (pinfunction "1_1") (pintype "passive"))
      (node (ref "U3") (pin "5") (pinfunction "VDD_5") (pintype "passive"))
    )
    (net (code "54") (name "Net-(U7-FB)") (class "Default")
      (node (ref "R2") (pin "2") (pinfunction "2_2") (pintype "passive"))
      (node (ref "R4") (pin "1") (pinfunction "1_1") (pintype "passive"))
      (node (ref "U7") (pin "3") (pinfunction "FB_3") (pintype "input"))
    )
    (net (code "55") (name "RTS") (class "Default")
      (node (ref "Q5") (pin "2") (pinfunction "E_2") (pintype "passive"))
      (node (ref "R17") (pin "1") (pinfunction "1_1") (pintype "passive"))
      (node (ref "U1") (pin "3") (pinfunction "~{RTS}_3") (pintype "output"))
    )
    (net (code "56") (name "USBDM") (class "Default")
      (node (ref "C10") (pin "2") (pinfunction "2_2") (pintype "passive"))
      (node (ref "R12") (pin "2") (pinfunction "2_2") (pintype "passive"))
      (node (ref "U1") (pin "16") (pinfunction "USBDM_16") (pintype "bidirectional"))
    )
    (net (code "57") (name "USBDP") (class "Default")
      (node (ref "C11") (pin "2") (pinfunction "2_2") (pintype "passive"))
      (node (ref "R13") (pin "2") (pinfunction "2_2") (pintype "passive"))
      (node (ref "U1") (pin "15") (pinfunction "USBDP_15") (pintype "bidirectional"))
    )
    (net (code "58") (name "VCC") (class "Default")
      (node (ref "C4") (pin "1") (pinfunction "1_1") (pintype "passive"))
      (node (ref "C5") (pin "1") (pinfunction "1_1") (pintype "passive"))
      (node (ref "C6") (pin "1") (pinfunction "1_1") (pintype "passive"))
      (node (ref "D3") (pin "1") (pinfunction "C_1") (pintype "passive"))
      (node (ref "LED1") (pin "1-VDD") (pinfunction "VDD_1-VDD") (pintype "power_in"))
      (node (ref "LED2") (pin "1-VDD") (pinfunction "VDD_1-VDD") (pintype "power_in"))
      (node (ref "LED3") (pin "1-VDD") (pinfunction "VDD_1-VDD") (pintype "power_in"))
      (node (ref "LED4") (pin "1-VDD") (pinfunction "VDD_1-VDD") (pintype "power_in"))
      (node (ref "LED5") (pin "1-VDD") (pinfunction "VDD_1-VDD") (pintype "power_in"))
      (node (ref "LED6") (pin "1-VDD") (pinfunction "VDD_1-VDD") (pintype "power_in"))
      (node (ref "REG1") (pin "P$3") (pinfunction "OUT_P$3") (pintype "bidirectional"))
      (node (ref "U$25") (pin "1") (pinfunction "IN_1") (pintype "input"))
    )
    (net (code "59") (name "VIN") (class "Default")
      (node (ref "C1") (pin "1") (pinfunction "1_1") (pintype "passive"))
      (node (ref "C15") (pin "1") (pinfunction "1_1") (pintype "passive"))
      (node (ref "C2") (pin "1") (pinfunction "1_1") (pintype "passive"))
      (node (ref "C3") (pin "1") (pinfunction "1_1") (pintype "passive"))
      (node (ref "L1") (pin "2") (pinfunction "2_2") (pintype "passive"))
      (node (ref "R3") (pin "2") (pinfunction "2_2") (pintype "passive"))
      (node (ref "R7") (pin "2") (pinfunction "2_2") (pintype "passive"))
      (node (ref "R9") (pin "1") (pinfunction "1_1") (pintype "passive"))
      (node (ref "REG1") (pin "P$1") (pinfunction "IN_P$1") (pintype "bidirectional"))
      (node (ref "S1") (pin "P3") (pinfunction "P$4_P3") (pintype "bidirectional"))
      (node (ref "U4") (pin "2") (pinfunction "VCC_2") (pintype "bidirectional"))
      (node (ref "U4") (pin "3") (pinfunction "VCC_3") (pintype "bidirectional"))
      (node (ref "U5") (pin "2") (pinfunction "VCC_2") (pintype "bidirectional"))
      (node (ref "U5") (pin "3") (pinfunction "VCC_3") (pintype "bidirectional"))
      (node (ref "U6") (pin "2") (pinfunction "VCC_2") (pintype "bidirectional"))
      (node (ref "U6") (pin "3") (pinfunction "VCC_3") (pintype "bidirectional"))
      (node (ref "U7") (pin "4") (pinfunction "EN_4") (pintype "input"))
      (node (ref "U7") (pin "5") (pinfunction "IN_5") (pintype "input"))
    )
    (net (code "60") (name "VOLTAGE") (class "Default")
      (node (ref "R3") (pin "1") (pinfunction "1_1") (pintype "passive"))
      (node (ref "R5") (pin "2") (pinfunction "2_2") (pintype "passive"))
      (node (ref "U2") (pin "6") (pinfunction "IO34_6") (pintype "input"))
    )
    (net (code "61") (name "VUSB") (class "Default")
      (node (ref "D3") (pin "2") (pinfunction "A_2") (pintype "passive"))
      (node (ref "J1") (pin "VBUS") (pinfunction "VBUS_VBUS") (pintype "bidirectional"))
      (node (ref "U1") (pin "20") (pinfunction "VCC_20") (pintype "power_in"))
    )
    (net (code "62") (name "unconnected-(LED6-DO-Pad2-DOUT)") (class "Default")
      (node (ref "LED6") (pin "2-DOUT") (pinfunction "DO_2-DOUT") (pintype "output"))
    )
    (net (code "63") (name "unconnected-(S1-P$3-PadP1)") (class "Default")
      (node (ref "S1") (pin "P1") (pinfunction "P$3_P1") (pintype "bidirectional"))
    )
    (net (code "64") (name "unconnected-(S1-P$6-PadP6)") (class "Default")
      (node (ref "S1") (pin "P6") (pinfunction "P$6_P6") (pintype "bidirectional"))
    )
    (net (code "65") (name "unconnected-(U1-CBUS0-Pad23)") (class "Default")
      (node (ref "U1") (pin "23") (pinfunction "CBUS0_23") (pintype "bidirectional"))
    )
    (net (code "66") (name "unconnected-(U1-CBUS1-Pad22)") (class "Default")
      (node (ref "U1") (pin "22") (pinfunction "CBUS1_22") (pintype "bidirectional"))
    )
    (net (code "67") (name "unconnected-(U1-CBUS2-Pad13)") (class "Default")
      (node (ref "U1") (pin "13") (pinfunction "CBUS2_13") (pintype "bidirectional"))
    )
    (net (code "68") (name "unconnected-(U1-CBUS3-Pad14)") (class "Default")
      (node (ref "U1") (pin "14") (pinfunction "CBUS3_14") (pintype "bidirectional"))
    )
    (net (code "69") (name "unconnected-(U1-CBUS4-Pad12)") (class "Default")
      (node (ref "U1") (pin "12") (pinfunction "CBUS4_12") (pintype "bidirectional"))
    )
    (net (code "70") (name "unconnected-(U1-OSCI-Pad27)") (class "Default")
      (node (ref "U1") (pin "27") (pinfunction "OSCI_27") (pintype "input"))
    )
    (net (code "71") (name "unconnected-(U1-OSCO-Pad28)") (class "Default")
      (node (ref "U1") (pin "28") (pinfunction "OSCO_28") (pintype "output"))
    )
    (net (code "72") (name "unconnected-(U1-~{CTS}-Pad11)") (class "Default")
      (node (ref "U1") (pin "11") (pinfunction "~{CTS}_11") (pintype "input"))
    )
    (net (code "73") (name "unconnected-(U1-~{DCD}-Pad10)") (class "Default")
      (node (ref "U1") (pin "10") (pinfunction "~{DCD}_10") (pintype "input"))
    )
    (net (code "74") (name "unconnected-(U1-~{DSR}-Pad9)") (class "Default")
      (node (ref "U1") (pin "9") (pinfunction "~{DSR}_9") (pintype "input"))
    )
    (net (code "75") (name "unconnected-(U1-~{RESET}-Pad19)") (class "Default")
      (node (ref "U1") (pin "19") (pinfunction "~{RESET}_19") (pintype "input"))
    )
    (net (code "76") (name "unconnected-(U1-~{RI}-Pad6)") (class "Default")
      (node (ref "U1") (pin "6") (pinfunction "~{RI}_6") (pintype "input"))
    )
    (net (code "77") (name "unconnected-(U2-IO2-Pad24)") (class "Default")
      (node (ref "U2") (pin "24") (pinfunction "IO2_24") (pintype "bidirectional"))
    )
    (net (code "78") (name "unconnected-(U2-IO5-Pad29)") (class "Default")
      (node (ref "U2") (pin "29") (pinfunction "IO5_29") (pintype "bidirectional"))
    )
    (net (code "79") (name "unconnected-(U2-IO12-Pad14)") (class "Default")
      (node (ref "U2") (pin "14") (pinfunction "IO12_14") (pintype "bidirectional"))
    )
    (net (code "80") (name "unconnected-(U2-IO15-Pad23)") (class "Default")
      (node (ref "U2") (pin "23") (pinfunction "IO15_23") (pintype "bidirectional"))
    )
    (net (code "81") (name "unconnected-(U2-IO35-Pad7)") (class "Default")
      (node (ref "U2") (pin "7") (pinfunction "IO35_7") (pintype "input"))
    )
    (net (code "82") (name "unconnected-(U2-NC-Pad17)") (class "Default")
      (node (ref "U2") (pin "17") (pinfunction "NC_17") (pintype "no_connect"))
    )
    (net (code "83") (name "unconnected-(U2-NC-Pad18)") (class "Default")
      (node (ref "U2") (pin "18") (pinfunction "NC_18") (pintype "no_connect"))
    )
    (net (code "84") (name "unconnected-(U2-NC-Pad19)") (class "Default")
      (node (ref "U2") (pin "19") (pinfunction "NC_19") (pintype "no_connect"))
    )
    (net (code "85") (name "unconnected-(U2-NC-Pad20)") (class "Default")
      (node (ref "U2") (pin "20") (pinfunction "NC_20") (pintype "no_connect"))
    )
    (net (code "86") (name "unconnected-(U2-NC-Pad21)") (class "Default")
      (node (ref "U2") (pin "21") (pinfunction "NC_21") (pintype "no_connect"))
    )
    (net (code "87") (name "unconnected-(U2-NC-Pad22)") (class "Default")
      (node (ref "U2") (pin "22") (pinfunction "NC_22") (pintype "no_connect"))
    )
    (net (code "88") (name "unconnected-(U2-NC1-Pad32)") (class "Default")
      (node (ref "U2") (pin "32") (pinfunction "NC1_32") (pintype "no_connect"))
    )
    (net (code "89") (name "unconnected-(U2-SENSOR_VN-Pad5)") (class "Default")
      (node (ref "U2") (pin "5") (pinfunction "SENSOR_VN_5") (pintype "input"))
    )
    (net (code "90") (name "unconnected-(U2-SENSOR_VP-Pad4)") (class "Default")
      (node (ref "U2") (pin "4") (pinfunction "SENSOR_VP_4") (pintype "input"))
    )
  )
)
